# 7_SurvBot_RCU_ExternalMemory.net
KiCad netlist of a schematic drawn in Altium Designer
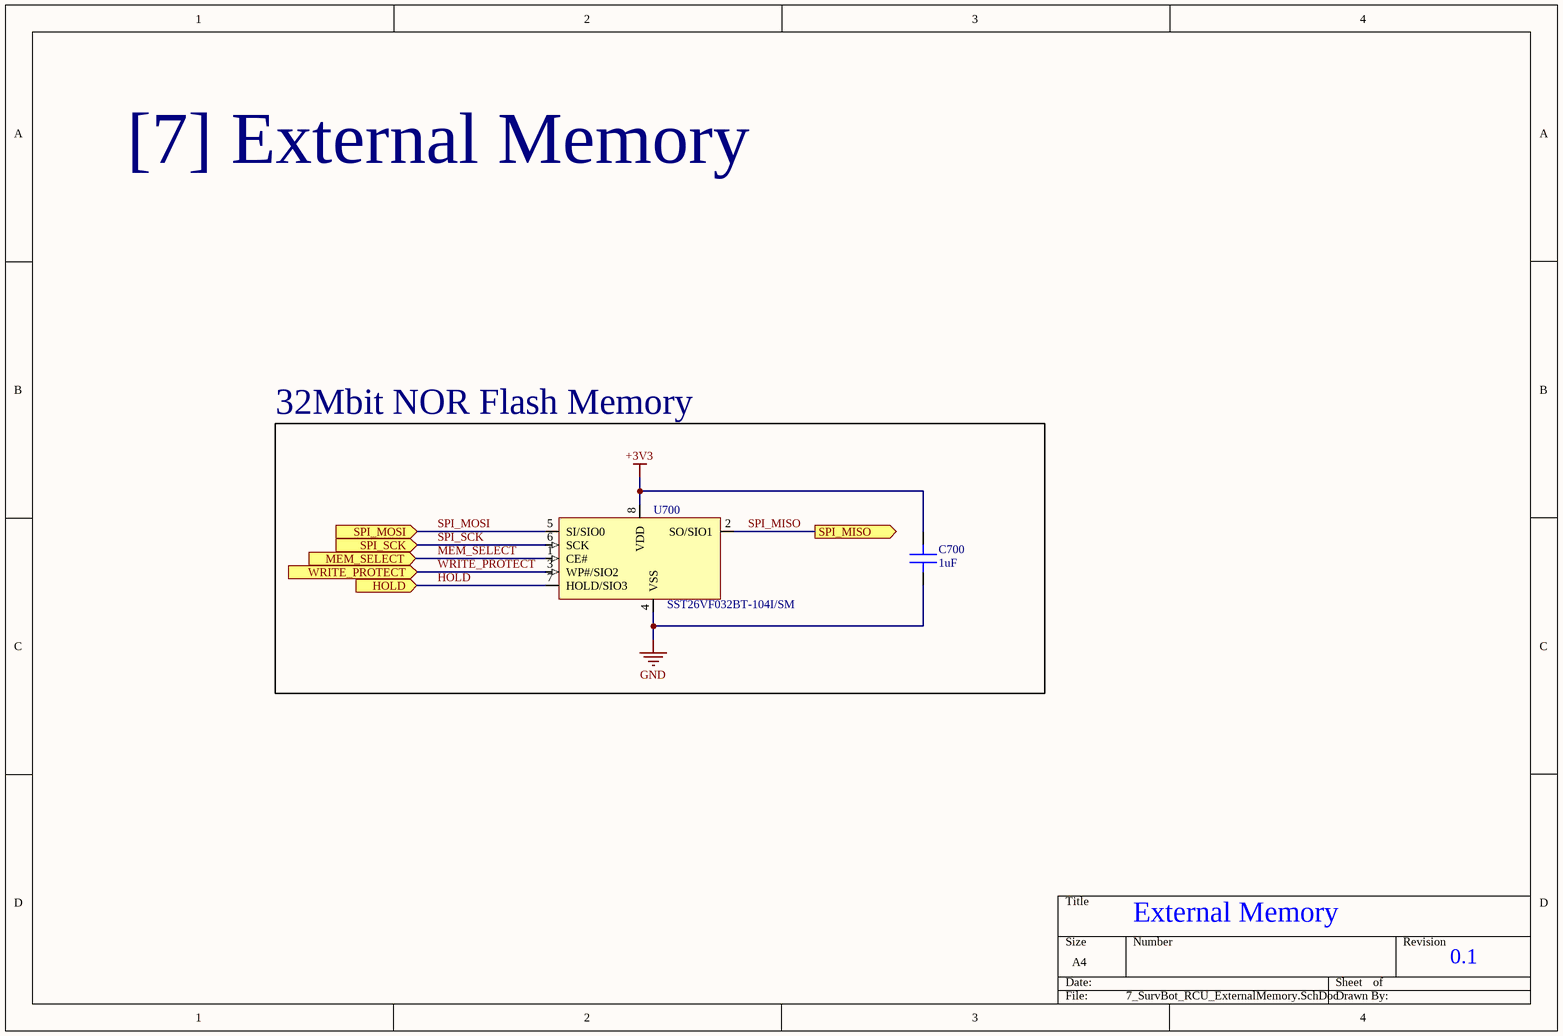
[diagram p0: 7_SurvBot_RCU_ExternalMemory.SchDoc]

(export (version "E")
  (design (tool "Eeschema 10.0.6"))
  (components
    (comp (ref "C700")
      (value "1uF")
      (footprint "CAP_0603")
      (description "1 µF ±10% 16V Ceramic Capacitor X7R 0603 (1608 Metric)")
      (fields (field (name "MANUFACTURER") "YAGEO") (field (name "MANUFACTURER PART #") "CC0603KRX7R7BB105"))
      (libsource (lib "GhaniLibrary") (part "CAP_1uF-16V-10%-0603"))
    )
    (comp (ref "U700")
      (value "SST26VF032BT-104I/SM")
      (footprint "8-SOIC, 5.26x5.25mm")
      (description "FLASH Memory IC 32Mbit SPI - Quad I/O 104 MHz 8-SOIJ")
      (fields (field (name "MANUFACTURER") "Microchip Tech"))
      (libsource (lib "GhaniLibrary") (part "IC_SST26VF032BT-104I/SM"))
    )
  )
  (nets
    (net (code "1") (name "+3V3") (class "Default")
      (node (ref "C700") (pin "2") (pinfunction "0_2") (pintype "passive"))
      (node (ref "U700") (pin "8") (pinfunction "VDD_8") (pintype "power_in"))
    )
    (net (code "2") (name "/HOLD") (class "Default")
      (node (ref "U700") (pin "7") (pinfunction "HOLD/SIO3_7") (pintype "bidirectional"))
    )
    (net (code "3") (name "/MEM_SELECT") (class "Default")
      (node (ref "U700") (pin "1") (pinfunction "CE#_1") (pintype "input"))
    )
    (net (code "4") (name "/SPI_MISO") (class "Default")
      (node (ref "U700") (pin "2") (pinfunction "SO/SIO1_2") (pintype "bidirectional"))
    )
    (net (code "5") (name "/SPI_MOSI") (class "Default")
      (node (ref "U700") (pin "5") (pinfunction "SI/SIO0_5") (pintype "bidirectional"))
    )
    (net (code "6") (name "/SPI_SCK") (class "Default")
      (node (ref "U700") (pin "6") (pinfunction "SCK_6") (pintype "input"))
    )
    (net (code "7") (name "/WRITE_PROTECT") (class "Default")
      (node (ref "U700") (pin "3") (pinfunction "WP#/SIO2_3") (pintype "input"))
    )
    (net (code "8") (name "GND") (class "Default")
      (node (ref "C700") (pin "1") (pinfunction "0_1") (pintype "passive"))
      (node (ref "U700") (pin "4") (pinfunction "VSS_4") (pintype "power_in"))
    )
  )
)
